# messen.net
KiCad netlist of a schematic drawn in EAGLE
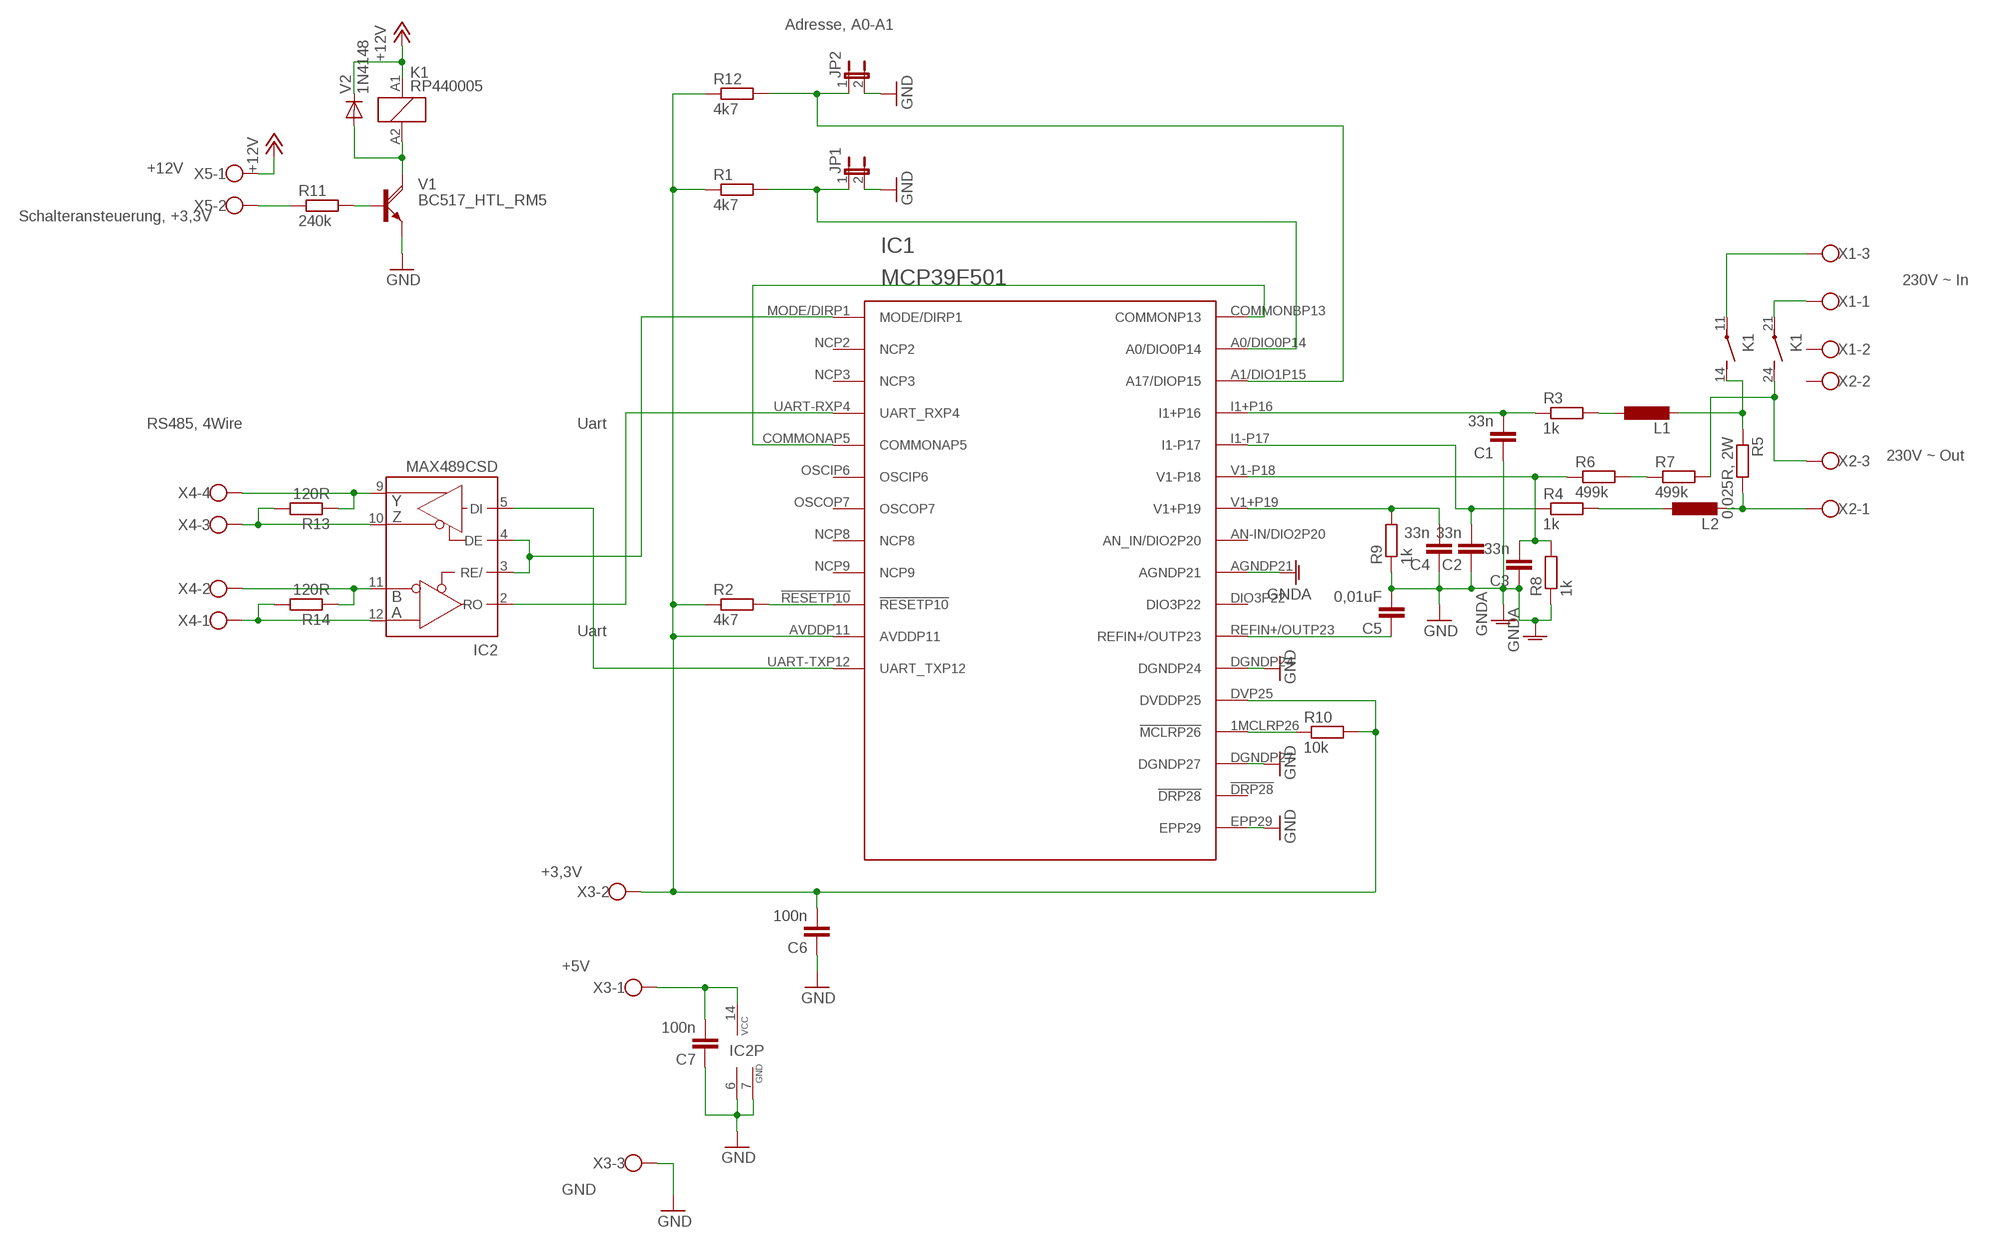
[diagram p0: schematic, sheet 1]

(export (version "E")
  (design (tool "Eeschema 10.0.6"))
  (components
    (comp (ref "C1")
      (value "33n")
      (footprint "eagle-import:C0805K")
      (libsource (lib "eagle-import") (part "C-EUC0805K"))
    )
    (comp (ref "C2")
      (value "33n")
      (footprint "eagle-import:C0805K")
      (libsource (lib "eagle-import") (part "C-EUC0805K"))
    )
    (comp (ref "C3")
      (value "33n")
      (footprint "eagle-import:C0805K")
      (libsource (lib "eagle-import") (part "C-EUC0805K"))
    )
    (comp (ref "C4")
      (value "33n")
      (footprint "eagle-import:C0805K")
      (libsource (lib "eagle-import") (part "C-EUC0805K"))
    )
    (comp (ref "C5")
      (value "0,01uF")
      (footprint "eagle-import:C0805K")
      (libsource (lib "eagle-import") (part "C-EUC0805K"))
    )
    (comp (ref "C6")
      (value "100n")
      (footprint "eagle-import:C0805K")
      (libsource (lib "eagle-import") (part "C-EUC0805K"))
    )
    (comp (ref "C7")
      (value "100n")
      (footprint "eagle-import:C0805K")
      (libsource (lib "eagle-import") (part "C-EUC0805K"))
    )
    (comp (ref "IC1")
      (value "MCP39F501")
      (footprint "eagle-import:MCP39F501")
      (libsource (lib "eagle-import") (part "MCP39F501"))
    )
    (comp (ref "IC2")
      (value "MAX489CSD")
      (footprint "eagle-import:SO14")
      (fields (field (name "MF") "MAXIM"))
      (libsource (lib "eagle-import") (part "MAX489CSD"))
    )
    (comp (ref "JP1")
      (value "JP1E")
      (footprint "eagle-import:JP1")
      (libsource (lib "eagle-import") (part "JP1E"))
    )
    (comp (ref "JP2")
      (value "JP1E")
      (footprint "eagle-import:JP1")
      (libsource (lib "eagle-import") (part "JP1E"))
    )
    (comp (ref "K1")
      (value "RP440005")
      (footprint "eagle-import:RP440")
      (libsource (lib "eagle-import") (part "RP44?0005"))
    )
    (comp (ref "L1")
      (value "L-EUL3230M")
      (footprint "eagle-import:L3230M")
      (libsource (lib "eagle-import") (part "L-EUL3230M"))
    )
    (comp (ref "L2")
      (value "L-EUL3230M")
      (footprint "eagle-import:L3230M")
      (libsource (lib "eagle-import") (part "L-EUL3230M"))
    )
    (comp (ref "R1")
      (value "4k7")
      (footprint "eagle-import:R0805")
      (libsource (lib "eagle-import") (part "R-EUR0805"))
    )
    (comp (ref "R2")
      (value "4k7")
      (footprint "eagle-import:0411_15")
      (libsource (lib "eagle-import") (part "R-EU0411/15"))
    )
    (comp (ref "R3")
      (value "1k")
      (footprint "eagle-import:R0805")
      (libsource (lib "eagle-import") (part "R-EUR0805"))
    )
    (comp (ref "R4")
      (value "1k")
      (footprint "eagle-import:R0805")
      (libsource (lib "eagle-import") (part "R-EUR0805"))
    )
    (comp (ref "R5")
      (value "0,025R, 2W")
      (footprint "eagle-import:R2512")
      (libsource (lib "eagle-import") (part "R-EUR2512"))
    )
    (comp (ref "R6")
      (value "499k")
      (footprint "eagle-import:0411_15")
      (libsource (lib "eagle-import") (part "R-EU0411/15"))
    )
    (comp (ref "R7")
      (value "499k")
      (footprint "eagle-import:0411_15")
      (libsource (lib "eagle-import") (part "R-EU0411/15"))
    )
    (comp (ref "R8")
      (value "1k")
      (footprint "eagle-import:R0805")
      (libsource (lib "eagle-import") (part "R-EUR0805"))
    )
    (comp (ref "R9")
      (value "1k")
      (footprint "eagle-import:R0805")
      (libsource (lib "eagle-import") (part "R-EUR0805"))
    )
    (comp (ref "R10")
      (value "10k")
      (footprint "eagle-import:0204_7")
      (libsource (lib "eagle-import") (part "R-EU0204/7"))
    )
    (comp (ref "R11")
      (value "240k")
      (footprint "eagle-import:0411_15")
      (libsource (lib "eagle-import") (part "R-EU0411/15"))
    )
    (comp (ref "R12")
      (value "4k7")
      (footprint "eagle-import:R0805")
      (libsource (lib "eagle-import") (part "R-EUR0805"))
    )
    (comp (ref "R13")
      (value "120R")
      (footprint "eagle-import:R0805")
      (libsource (lib "eagle-import") (part "R-EUR0805"))
    )
    (comp (ref "R14")
      (value "120R")
      (footprint "eagle-import:R0805")
      (libsource (lib "eagle-import") (part "R-EUR0805"))
    )
    (comp (ref "V1")
      (value "BC517_HTL_RM5")
      (footprint "eagle-import:TO92_RM5")
      (libsource (lib "eagle-import") (part "BC517_HTL_RM5"))
    )
    (comp (ref "V2")
      (value "1N4148")
      (footprint "eagle-import:DO35-7")
      (libsource (lib "eagle-import") (part "1N4148_HTL"))
    )
    (comp (ref "X1")
      (value "W237-103_R")
      (footprint "eagle-import:W237-103_R")
      (libsource (lib "eagle-import") (part "W237-103_R"))
    )
    (comp (ref "X2")
      (value "W237-103_R")
      (footprint "eagle-import:W237-103_R")
      (libsource (lib "eagle-import") (part "W237-103_R"))
    )
    (comp (ref "X3")
      (value "W237-103_L")
      (footprint "eagle-import:W237-103_L")
      (libsource (lib "eagle-import") (part "W237-103_L"))
    )
    (comp (ref "X4")
      (value "W237-04P_L")
      (footprint "eagle-import:W237-4P_L")
      (libsource (lib "eagle-import") (part "W237-04P_L"))
    )
    (comp (ref "X5")
      (value "W237-102_L")
      (footprint "eagle-import:W237-102_L")
      (libsource (lib "eagle-import") (part "W237-102_L"))
    )
  )
  (nets
    (net (code "1") (name "+12V") (class "Default")
      (node (ref "K1") (pin "A1") (pinfunction "1_A1") (pintype "passive"))
      (node (ref "V2") (pin "C") (pinfunction "C_C") (pintype "passive"))
      (node (ref "X5") (pin "1") (pinfunction "KL_1") (pintype "passive"))
    )
    (net (code "2") (name "GND") (class "Default")
      (node (ref "C1") (pin "1") (pinfunction "1_1") (pintype "passive"))
      (node (ref "C2") (pin "1") (pinfunction "1_1") (pintype "passive"))
      (node (ref "C3") (pin "1") (pinfunction "1_1") (pintype "passive"))
      (node (ref "C4") (pin "1") (pinfunction "1_1") (pintype "passive"))
      (node (ref "C5") (pin "2") (pinfunction "2_2") (pintype "passive"))
      (node (ref "C6") (pin "1") (pinfunction "1_1") (pintype "passive"))
      (node (ref "C7") (pin "1") (pinfunction "1_1") (pintype "passive"))
      (node (ref "IC1") (pin "AGNDP21") (pinfunction "AGNDP21_AGNDP21") (pintype "bidirectional"))
      (node (ref "IC1") (pin "DGNDP24") (pinfunction "DGNDP24_DGNDP24") (pintype "bidirectional"))
      (node (ref "IC1") (pin "DGNDP27") (pinfunction "DGNDP27_DGNDP27") (pintype "bidirectional"))
      (node (ref "IC1") (pin "EPP29") (pinfunction "EPP29_EPP29") (pintype "bidirectional"))
      (node (ref "IC2") (pin "6") (pinfunction "GND_6") (pintype "power_in"))
      (node (ref "IC2") (pin "7") (pinfunction "GND_7") (pintype "power_in"))
      (node (ref "JP1") (pin "2") (pinfunction "2_2") (pintype "passive"))
      (node (ref "JP2") (pin "2") (pinfunction "2_2") (pintype "passive"))
      (node (ref "R8") (pin "1") (pinfunction "1_1") (pintype "passive"))
      (node (ref "R9") (pin "1") (pinfunction "1_1") (pintype "passive"))
      (node (ref "V1") (pin "1") (pinfunction "E_1") (pintype "passive"))
      (node (ref "X3") (pin "3") (pinfunction "KL_3") (pintype "passive"))
    )
    (net (code "3") (name "Net-(C1-Pad2)") (class "Default")
      (node (ref "C1") (pin "2") (pinfunction "2_2") (pintype "passive"))
      (node (ref "IC1") (pin "I1+P16") (pinfunction "I1+P16_I1+P16") (pintype "bidirectional"))
      (node (ref "R3") (pin "1") (pinfunction "1_1") (pintype "passive"))
    )
    (net (code "4") (name "Net-(C2-Pad2)") (class "Default")
      (node (ref "C2") (pin "2") (pinfunction "2_2") (pintype "passive"))
      (node (ref "IC1") (pin "I1-P17") (pinfunction "I1-P17_I1-P17") (pintype "bidirectional"))
      (node (ref "R4") (pin "1") (pinfunction "1_1") (pintype "passive"))
    )
    (net (code "5") (name "Net-(C3-Pad2)") (class "Default")
      (node (ref "C3") (pin "2") (pinfunction "2_2") (pintype "passive"))
      (node (ref "IC1") (pin "V1-P18") (pinfunction "V1-P18_V1-P18") (pintype "bidirectional"))
      (node (ref "R6") (pin "1") (pinfunction "1_1") (pintype "passive"))
      (node (ref "R8") (pin "2") (pinfunction "2_2") (pintype "passive"))
    )
    (net (code "6") (name "Net-(C4-Pad2)") (class "Default")
      (node (ref "C4") (pin "2") (pinfunction "2_2") (pintype "passive"))
      (node (ref "IC1") (pin "V1+P19") (pinfunction "V1+P19_V1+P19") (pintype "bidirectional"))
      (node (ref "R9") (pin "2") (pinfunction "2_2") (pintype "passive"))
    )
    (net (code "7") (name "Net-(C5-Pad1)") (class "Default")
      (node (ref "C5") (pin "1") (pinfunction "1_1") (pintype "passive"))
      (node (ref "IC1") (pin "REFIN+/OUTP23") (pinfunction "REFIN+/OUTP23_REFIN+/OUTP23") (pintype "bidirectional"))
    )
    (net (code "8") (name "Net-(IC1-A17{slash}DIOP15)") (class "Default")
      (node (ref "IC1") (pin "A1/DIO1P15") (pinfunction "A17/DIOP15_A1/DIO1P15") (pintype "bidirectional"))
      (node (ref "JP2") (pin "1") (pinfunction "1_1") (pintype "passive"))
      (node (ref "R12") (pin "2") (pinfunction "2_2") (pintype "passive"))
    )
    (net (code "9") (name "Net-(IC1-COMMONP13)") (class "Default")
      (node (ref "IC1") (pin "COMMONAP5") (pinfunction "COMMONAP5_COMMONAP5") (pintype "bidirectional"))
      (node (ref "IC1") (pin "COMMONBP13") (pinfunction "COMMONP13_COMMONBP13") (pintype "bidirectional"))
    )
    (net (code "10") (name "Net-(IC1-DVDDP25)") (class "Default")
      (node (ref "C6") (pin "2") (pinfunction "2_2") (pintype "passive"))
      (node (ref "IC1") (pin "AVDDP11") (pinfunction "AVDDP11_AVDDP11") (pintype "bidirectional"))
      (node (ref "IC1") (pin "DVP25") (pinfunction "DVDDP25_DVP25") (pintype "bidirectional"))
      (node (ref "R1") (pin "1") (pinfunction "1_1") (pintype "passive"))
      (node (ref "R10") (pin "2") (pinfunction "2_2") (pintype "passive"))
      (node (ref "R12") (pin "1") (pinfunction "1_1") (pintype "passive"))
      (node (ref "R2") (pin "1") (pinfunction "1_1") (pintype "passive"))
      (node (ref "X3") (pin "2") (pinfunction "KL_2") (pintype "passive"))
    )
    (net (code "11") (name "Net-(IC1-PadA0{slash}DIO0P14)") (class "Default")
      (node (ref "IC1") (pin "A0/DIO0P14") (pinfunction "A0/DIO0P14_A0/DIO0P14") (pintype "bidirectional"))
      (node (ref "JP1") (pin "1") (pinfunction "1_1") (pintype "passive"))
      (node (ref "R1") (pin "2") (pinfunction "2_2") (pintype "passive"))
    )
    (net (code "12") (name "Net-(IC1-UART_RXP4)") (class "Default")
      (node (ref "IC1") (pin "UART-RXP4") (pinfunction "UART_RXP4_UART-RXP4") (pintype "bidirectional"))
      (node (ref "IC2") (pin "2") (pinfunction "RO_2") (pintype "output"))
    )
    (net (code "13") (name "Net-(IC1-UART_TXP12)") (class "Default")
      (node (ref "IC1") (pin "UART-TXP12") (pinfunction "UART_TXP12_UART-TXP12") (pintype "bidirectional"))
      (node (ref "IC2") (pin "5") (pinfunction "DI_5") (pintype "input"))
    )
    (net (code "14") (name "Net-(IC1-~{MCLRP26})") (class "Default")
      (node (ref "IC1") (pin "1MCLRP26") (pinfunction "~{MCLRP26}_1MCLRP26") (pintype "bidirectional"))
      (node (ref "R10") (pin "1") (pinfunction "1_1") (pintype "passive"))
    )
    (net (code "15") (name "Net-(IC1-~{RESETP10})") (class "Default")
      (node (ref "IC1") (pin "!RESETP10") (pinfunction "~{RESETP10}_!RESETP10") (pintype "bidirectional"))
      (node (ref "R2") (pin "2") (pinfunction "2_2") (pintype "passive"))
    )
    (net (code "16") (name "Net-(IC2D-A)") (class "Default")
      (node (ref "IC2") (pin "12") (pinfunction "A_12") (pintype "passive"))
      (node (ref "R14") (pin "2") (pinfunction "2_2") (pintype "passive"))
      (node (ref "X4") (pin "1") (pinfunction "KL_1") (pintype "passive"))
    )
    (net (code "17") (name "Net-(IC2D-B)") (class "Default")
      (node (ref "IC2") (pin "11") (pinfunction "B_11") (pintype "passive"))
      (node (ref "R14") (pin "1") (pinfunction "1_1") (pintype "passive"))
      (node (ref "X4") (pin "2") (pinfunction "KL_2") (pintype "passive"))
    )
    (net (code "18") (name "Net-(IC2D-DE)") (class "Default")
      (node (ref "IC1") (pin "MODE/DIRP1") (pinfunction "MODE/DIRP1_MODE/DIRP1") (pintype "bidirectional"))
      (node (ref "IC2") (pin "3") (pinfunction "RE/_3") (pintype "input"))
      (node (ref "IC2") (pin "4") (pinfunction "DE_4") (pintype "input"))
    )
    (net (code "19") (name "Net-(IC2D-Y)") (class "Default")
      (node (ref "IC2") (pin "9") (pinfunction "Y_9") (pintype "passive"))
      (node (ref "R13") (pin "1") (pinfunction "1_1") (pintype "passive"))
      (node (ref "X4") (pin "4") (pinfunction "KL_4") (pintype "passive"))
    )
    (net (code "20") (name "Net-(IC2D-Z)") (class "Default")
      (node (ref "IC2") (pin "10") (pinfunction "Z_10") (pintype "passive"))
      (node (ref "R13") (pin "2") (pinfunction "2_2") (pintype "passive"))
      (node (ref "X4") (pin "3") (pinfunction "KL_3") (pintype "passive"))
    )
    (net (code "21") (name "Net-(IC2E-VCC)") (class "Default")
      (node (ref "C7") (pin "2") (pinfunction "2_2") (pintype "passive"))
      (node (ref "IC2") (pin "14") (pinfunction "VCC_14") (pintype "power_in"))
      (node (ref "X3") (pin "1") (pinfunction "KL_1") (pintype "passive"))
    )
    (net (code "22") (name "Net-(K1A-2)") (class "Default")
      (node (ref "K1") (pin "A2") (pinfunction "2_A2") (pintype "passive"))
      (node (ref "V1") (pin "3") (pinfunction "C_3") (pintype "passive"))
      (node (ref "V2") (pin "A") (pinfunction "A_A") (pintype "passive"))
    )
    (net (code "23") (name "Net-(K1B-P)") (class "Default")
      (node (ref "K1") (pin "11") (pinfunction "P_11") (pintype "passive"))
      (node (ref "X1") (pin "3") (pinfunction "KL_3") (pintype "passive"))
    )
    (net (code "24") (name "Net-(K1B-S)") (class "Default")
      (node (ref "K1") (pin "14") (pinfunction "S_14") (pintype "passive"))
      (node (ref "L1") (pin "2") (pinfunction "2_2") (pintype "passive"))
      (node (ref "R5") (pin "1") (pinfunction "1_1") (pintype "passive"))
    )
    (net (code "25") (name "Net-(K1C-P)") (class "Default")
      (node (ref "K1") (pin "21") (pinfunction "P_21") (pintype "passive"))
      (node (ref "X1") (pin "1") (pinfunction "KL_1") (pintype "passive"))
    )
    (net (code "26") (name "Net-(K1C-S)") (class "Default")
      (node (ref "K1") (pin "24") (pinfunction "S_24") (pintype "passive"))
      (node (ref "R7") (pin "2") (pinfunction "2_2") (pintype "passive"))
      (node (ref "X2") (pin "3") (pinfunction "KL_3") (pintype "passive"))
    )
    (net (code "27") (name "Net-(L1-Pad1)") (class "Default")
      (node (ref "L1") (pin "1") (pinfunction "1_1") (pintype "passive"))
      (node (ref "R3") (pin "2") (pinfunction "2_2") (pintype "passive"))
    )
    (net (code "28") (name "Net-(L2-Pad1)") (class "Default")
      (node (ref "L2") (pin "1") (pinfunction "1_1") (pintype "passive"))
      (node (ref "R4") (pin "2") (pinfunction "2_2") (pintype "passive"))
    )
    (net (code "29") (name "Net-(R6-Pad2)") (class "Default")
      (node (ref "R6") (pin "2") (pinfunction "2_2") (pintype "passive"))
      (node (ref "R7") (pin "1") (pinfunction "1_1") (pintype "passive"))
    )
    (net (code "30") (name "Net-(V1-B)") (class "Default")
      (node (ref "R11") (pin "2") (pinfunction "2_2") (pintype "passive"))
      (node (ref "V1") (pin "2") (pinfunction "B_2") (pintype "passive"))
    )
    (net (code "31") (name "Net-(X2A-KL)") (class "Default")
      (node (ref "L2") (pin "2") (pinfunction "2_2") (pintype "passive"))
      (node (ref "R5") (pin "2") (pinfunction "2_2") (pintype "passive"))
      (node (ref "X2") (pin "1") (pinfunction "KL_1") (pintype "passive"))
    )
    (net (code "32") (name "Net-(X5B-KL)") (class "Default")
      (node (ref "R11") (pin "1") (pinfunction "1_1") (pintype "passive"))
      (node (ref "X5") (pin "2") (pinfunction "KL_2") (pintype "passive"))
    )
    (net (code "33") (name "unconnected-(IC1-AN_IN{slash}DIO2P20-PadAN-IN{slash}DIO2P20)") (class "Default")
      (node (ref "IC1") (pin "AN-IN/DIO2P20") (pinfunction "AN_IN/DIO2P20_AN-IN/DIO2P20") (pintype "bidirectional"))
    )
    (net (code "34") (name "unconnected-(IC1-PadDIO3P22)") (class "Default")
      (node (ref "IC1") (pin "DIO3P22") (pinfunction "DIO3P22_DIO3P22") (pintype "bidirectional"))
    )
    (net (code "35") (name "unconnected-(IC1-PadNCP2)") (class "Default")
      (node (ref "IC1") (pin "NCP2") (pinfunction "NCP2_NCP2") (pintype "bidirectional"))
    )
    (net (code "36") (name "unconnected-(IC1-PadNCP3)") (class "Default")
      (node (ref "IC1") (pin "NCP3") (pinfunction "NCP3_NCP3") (pintype "bidirectional"))
    )
    (net (code "37") (name "unconnected-(IC1-PadNCP8)") (class "Default")
      (node (ref "IC1") (pin "NCP8") (pinfunction "NCP8_NCP8") (pintype "bidirectional"))
    )
    (net (code "38") (name "unconnected-(IC1-PadNCP9)") (class "Default")
      (node (ref "IC1") (pin "NCP9") (pinfunction "NCP9_NCP9") (pintype "bidirectional"))
    )
    (net (code "39") (name "unconnected-(IC1-PadOSCIP6)") (class "Default")
      (node (ref "IC1") (pin "OSCIP6") (pinfunction "OSCIP6_OSCIP6") (pintype "bidirectional"))
    )
    (net (code "40") (name "unconnected-(IC1-PadOSCOP7)") (class "Default")
      (node (ref "IC1") (pin "OSCOP7") (pinfunction "OSCOP7_OSCOP7") (pintype "bidirectional"))
    )
    (net (code "41") (name "unconnected-(IC1-~{DRP28}-Pad!DRP28)") (class "Default")
      (node (ref "IC1") (pin "!DRP28") (pinfunction "~{DRP28}_!DRP28") (pintype "bidirectional"))
    )
    (net (code "42") (name "unconnected-(X1B-KL-Pad2)") (class "Default")
      (node (ref "X1") (pin "2") (pinfunction "KL_2") (pintype "passive"))
    )
    (net (code "43") (name "unconnected-(X2B-KL-Pad2)") (class "Default")
      (node (ref "X2") (pin "2") (pinfunction "KL_2") (pintype "passive"))
    )
  )
)
